# powersupply_example.net
KiCad netlist of a schematic drawn in EAGLE
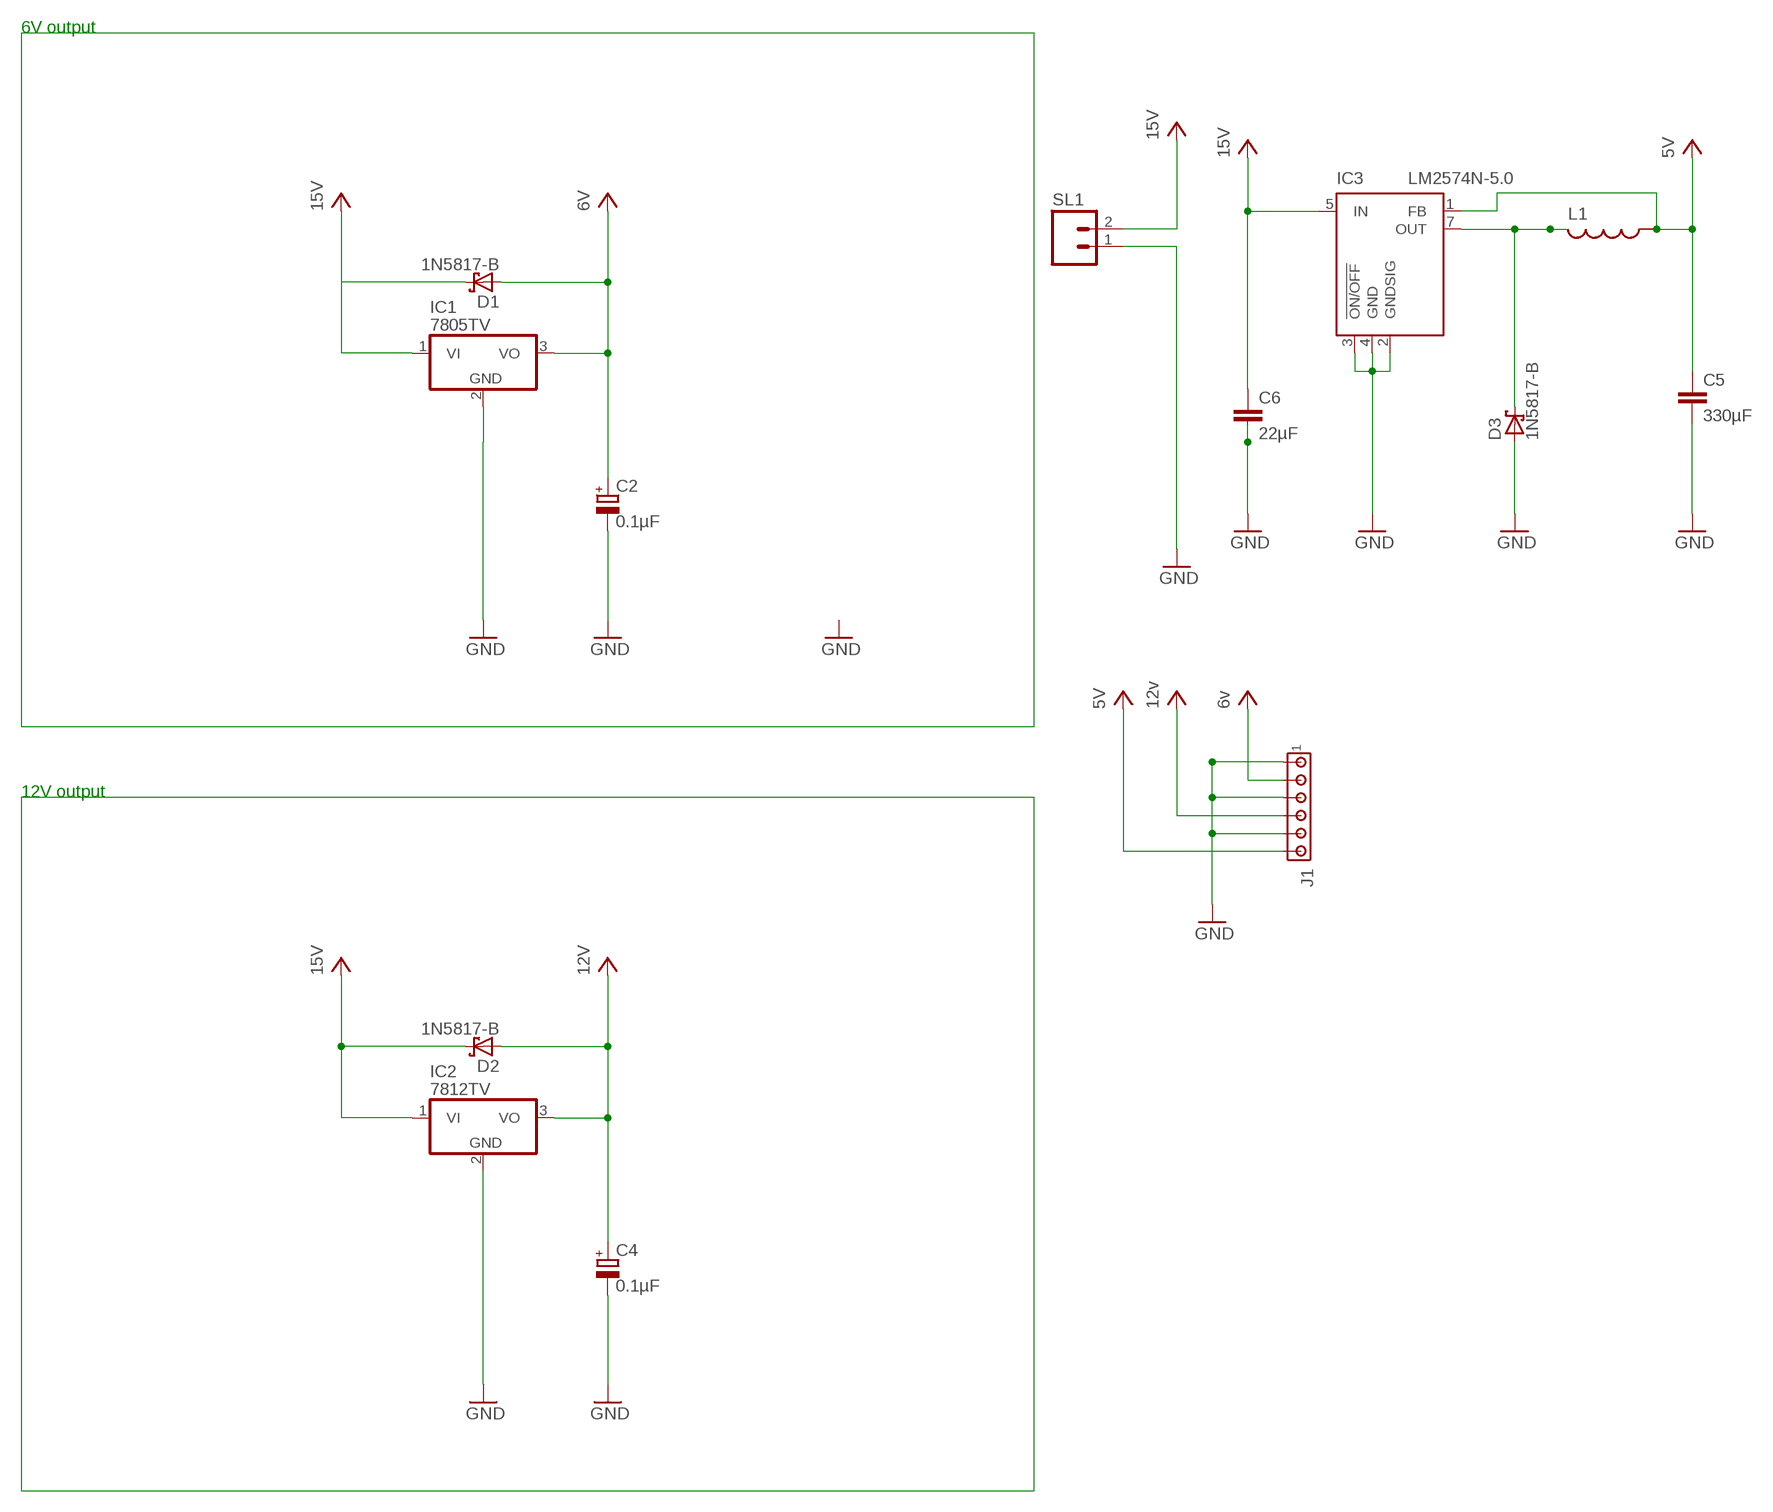
[diagram p0: schematic, sheet 1]

(export (version "E")
  (design (tool "Eeschema 10.0.6"))
  (components
    (comp (ref "C2")
      (value "0.1µF")
      (footprint "eagle-import:E2,5-5")
      (libsource (lib "eagle-import") (part "CPOL-EUE2.5-5"))
    )
    (comp (ref "C4")
      (value "0.1µF")
      (footprint "eagle-import:E2,5-5")
      (libsource (lib "eagle-import") (part "CPOL-EUE2.5-5"))
    )
    (comp (ref "C5")
      (value "330µF")
      (footprint "eagle-import:C025-040X050")
      (libsource (lib "eagle-import") (part "C-EU025-040X050"))
    )
    (comp (ref "C6")
      (value "22µF")
      (footprint "eagle-import:C025-040X050")
      (libsource (lib "eagle-import") (part "C-EU025-040X050"))
    )
    (comp (ref "D1")
      (value "1N5817-B")
      (footprint "eagle-import:DO41-7.6")
      (libsource (lib "eagle-import") (part "1N5817-B"))
    )
    (comp (ref "D2")
      (value "1N5817-B")
      (footprint "eagle-import:DO41-7.6")
      (libsource (lib "eagle-import") (part "1N5817-B"))
    )
    (comp (ref "D3")
      (value "1N5817-B")
      (footprint "eagle-import:DO41-7.6")
      (libsource (lib "eagle-import") (part "1N5817-B"))
    )
    (comp (ref "IC1")
      (value "7805TV")
      (footprint "eagle-import:TO220V")
      (libsource (lib "eagle-import") (part "78TV05"))
    )
    (comp (ref "IC2")
      (value "7812TV")
      (footprint "eagle-import:TO220V")
      (libsource (lib "eagle-import") (part "78TV12"))
    )
    (comp (ref "IC3")
      (value "LM2574N-5.0")
      (footprint "eagle-import:DIL08")
      (libsource (lib "eagle-import") (part "LM2574?-N5.0"))
    )
    (comp (ref "J1")
      (value "MTA06-100")
      (footprint "eagle-import:10X06MTA")
      (libsource (lib "eagle-import") (part "MTA06-100"))
    )
    (comp (ref "L1")
      (value "L-US0204/7")
      (footprint "eagle-import:0204_7")
      (libsource (lib "eagle-import") (part "L-US0204/7"))
    )
    (comp (ref "SL1")
      (value "M02")
      (footprint "eagle-import:02P")
      (libsource (lib "eagle-import") (part "M02"))
    )
  )
  (nets
    (net (code "1") (name "5V") (class "Default")
      (node (ref "C5") (pin "1") (pinfunction "1_1") (pintype "passive"))
      (node (ref "IC3") (pin "1") (pinfunction "FB_1") (pintype "input"))
      (node (ref "J1") (pin "6") (pinfunction "6_6") (pintype "passive"))
      (node (ref "L1") (pin "1") (pinfunction "1_1") (pintype "passive"))
    )
    (net (code "2") (name "6V") (class "Default")
      (node (ref "C2") (pin "+") (pinfunction "+_+") (pintype "passive"))
      (node (ref "D1") (pin "A") (pinfunction "A_A") (pintype "passive"))
      (node (ref "IC1") (pin "3") (pinfunction "VO_3") (pintype "passive"))
      (node (ref "J1") (pin "2") (pinfunction "2_2") (pintype "passive"))
    )
    (net (code "3") (name "12V") (class "Default")
      (node (ref "C4") (pin "+") (pinfunction "+_+") (pintype "passive"))
      (node (ref "D2") (pin "A") (pinfunction "A_A") (pintype "passive"))
      (node (ref "IC2") (pin "3") (pinfunction "VO_3") (pintype "passive"))
      (node (ref "J1") (pin "4") (pinfunction "4_4") (pintype "passive"))
    )
    (net (code "4") (name "15V") (class "Default")
      (node (ref "C6") (pin "1") (pinfunction "1_1") (pintype "passive"))
      (node (ref "D1") (pin "C") (pinfunction "C_C") (pintype "passive"))
      (node (ref "D2") (pin "C") (pinfunction "C_C") (pintype "passive"))
      (node (ref "IC1") (pin "1") (pinfunction "VI_1") (pintype "input"))
      (node (ref "IC2") (pin "1") (pinfunction "VI_1") (pintype "input"))
      (node (ref "IC3") (pin "5") (pinfunction "IN_5") (pintype "input"))
      (node (ref "SL1") (pin "2") (pinfunction "2_2") (pintype "passive"))
    )
    (net (code "5") (name "GND") (class "Default")
      (node (ref "C2") (pin "-") (pinfunction "-_-") (pintype "passive"))
      (node (ref "C4") (pin "-") (pinfunction "-_-") (pintype "passive"))
      (node (ref "C5") (pin "2") (pinfunction "2_2") (pintype "passive"))
      (node (ref "C6") (pin "2") (pinfunction "2_2") (pintype "passive"))
      (node (ref "D3") (pin "A") (pinfunction "A_A") (pintype "passive"))
      (node (ref "IC1") (pin "2") (pinfunction "GND_2") (pintype "passive"))
      (node (ref "IC2") (pin "2") (pinfunction "GND_2") (pintype "passive"))
      (node (ref "IC3") (pin "2") (pinfunction "GNDSIG_2") (pintype "input"))
      (node (ref "IC3") (pin "3") (pinfunction "~{ON/OFF}_3") (pintype "input"))
      (node (ref "IC3") (pin "4") (pinfunction "GND_4") (pintype "power_in"))
      (node (ref "J1") (pin "1") (pinfunction "1_1") (pintype "passive"))
      (node (ref "J1") (pin "3") (pinfunction "3_3") (pintype "passive"))
      (node (ref "J1") (pin "5") (pinfunction "5_5") (pintype "passive"))
      (node (ref "SL1") (pin "1") (pinfunction "1_1") (pintype "passive"))
    )
    (net (code "6") (name "Net-(IC3-OUT)") (class "Default")
      (node (ref "D3") (pin "C") (pinfunction "C_C") (pintype "passive"))
      (node (ref "IC3") (pin "7") (pinfunction "OUT_7") (pintype "passive"))
      (node (ref "L1") (pin "2") (pinfunction "2_2") (pintype "passive"))
    )
  )
)
